# Solar_Points.net
KiCad netlist of a schematic drawn in EAGLE
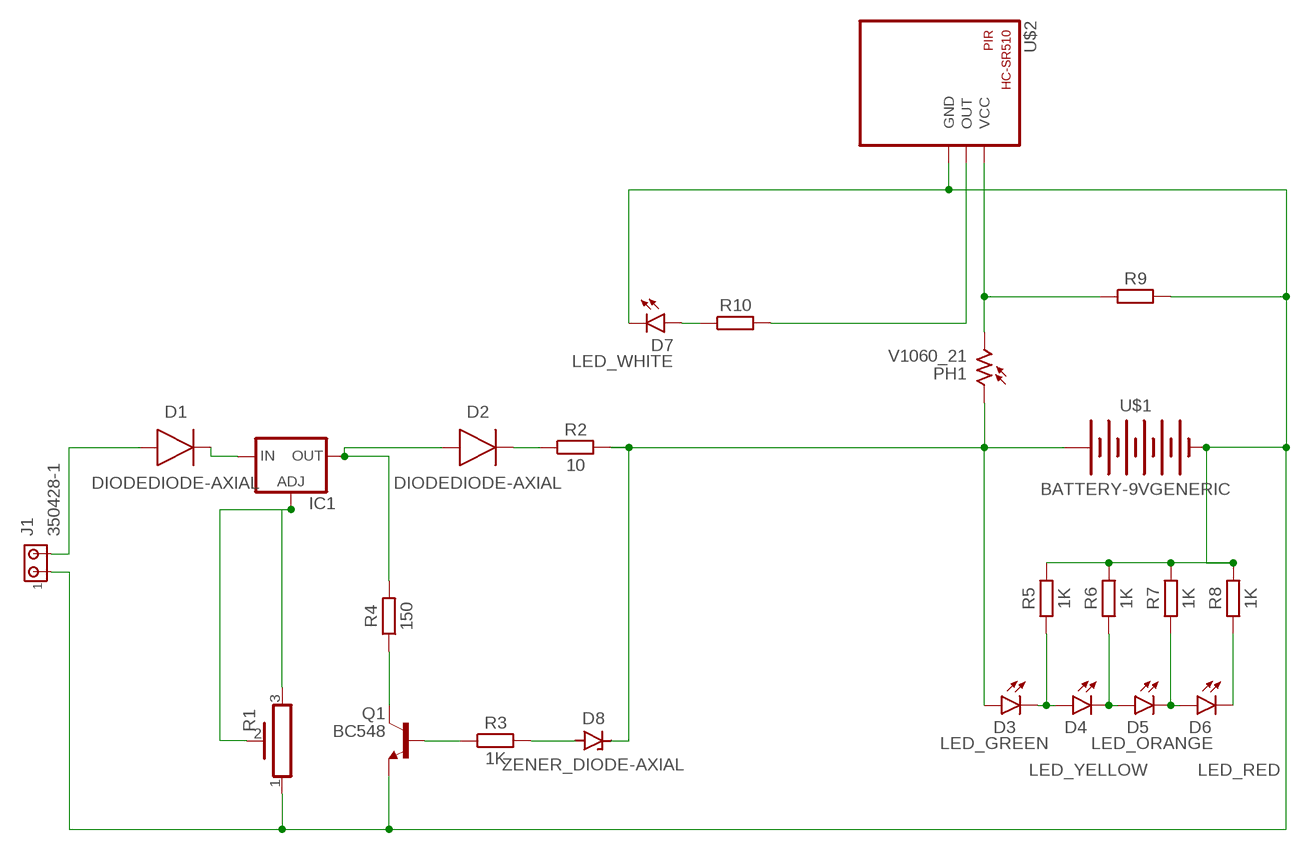
[diagram p0: schematic, sheet 1]

(export (version "E")
  (design (tool "Eeschema 10.0.6"))
  (components
    (comp (ref "D1")
      (value "DIODEDIODE-AXIAL")
      (footprint "eagle-import:DIODE-AXIAL")
      (libsource (lib "eagle-import") (part "DIODEDIODE-AXIAL"))
    )
    (comp (ref "D2")
      (value "DIODEDIODE-AXIAL")
      (footprint "eagle-import:DIODE-AXIAL")
      (libsource (lib "eagle-import") (part "DIODEDIODE-AXIAL"))
    )
    (comp (ref "D3")
      (value "LED_GREEN")
      (footprint "eagle-import:LEDRD254W60D565H860B_G")
      (libsource (lib "eagle-import") (part "LED_RADIALGREEN_"))
    )
    (comp (ref "D4")
      (value "LED_YELLOW")
      (footprint "eagle-import:LEDRD254W60D565H860B_Y")
      (libsource (lib "eagle-import") (part "LED_RADIALYELLOW_"))
    )
    (comp (ref "D5")
      (value "LED_ORANGE")
      (footprint "eagle-import:LEDRD254W60D565H860B_O")
      (libsource (lib "eagle-import") (part "LED_RADIALORANGE_"))
    )
    (comp (ref "D6")
      (value "LED_RED")
      (footprint "eagle-import:LEDRD254W60D565H860B")
      (libsource (lib "eagle-import") (part "LED_RADIALRED_"))
    )
    (comp (ref "D7")
      (value "LED_WHITE")
      (footprint "eagle-import:LEDRD254W60D565H860B_W")
      (libsource (lib "eagle-import") (part "LED_RADIALWHITE_"))
    )
    (comp (ref "D8")
      (value "ZENER_DIODE-AXIAL")
      (footprint "eagle-import:DIODE-AXIAL")
      (libsource (lib "eagle-import") (part "ZENER_DIODE-AXIAL"))
    )
    (comp (ref "IC1")
      (value "LM317TL")
      (footprint "eagle-import:317TL")
      (libsource (lib "eagle-import") (part "LM317TL"))
    )
    (comp (ref "J1")
      (value "350428-1")
      (footprint "eagle-import:350428-1")
      (libsource (lib "eagle-import") (part "350428-1"))
    )
    (comp (ref "PH1")
      (value "V1060_21")
      (footprint "eagle-import:TO-5_V10")
      (libsource (lib "eagle-import") (part "?1060V_21"))
    )
    (comp (ref "Q1")
      (value "BC548")
      (footprint "eagle-import:TO92")
      (libsource (lib "eagle-import") (part "NPN_TO92_"))
    )
    (comp (ref "R1")
      (value "POT_PV36Z")
      (footprint "eagle-import:PV36Z")
      (fields (field (name "MANUFACTURER") "BOURNS") (field (name "MPN") "PV36Z"))
      (libsource (lib "eagle-import") (part "POT_PV36Z"))
    )
    (comp (ref "R2")
      (value "10")
      (footprint "eagle-import:RESAD1176W63L850D250B")
      (libsource (lib "eagle-import") (part "RESISTOR_AXIAL-11.7MM-PITCH_"))
    )
    (comp (ref "R3")
      (value "1K")
      (footprint "eagle-import:RESAD1176W63L850D250B")
      (libsource (lib "eagle-import") (part "RESISTOR_AXIAL-11.7MM-PITCH_"))
    )
    (comp (ref "R4")
      (value "150")
      (footprint "eagle-import:RESAD1176W63L850D250B")
      (libsource (lib "eagle-import") (part "RESISTOR_AXIAL-11.7MM-PITCH_"))
    )
    (comp (ref "R5")
      (value "1K")
      (footprint "eagle-import:RESAD1176W63L850D250B")
      (libsource (lib "eagle-import") (part "RESISTOR_AXIAL-11.7MM-PITCH_"))
    )
    (comp (ref "R6")
      (value "1K")
      (footprint "eagle-import:RESAD1176W63L850D250B")
      (libsource (lib "eagle-import") (part "RESISTOR_AXIAL-11.7MM-PITCH_"))
    )
    (comp (ref "R7")
      (value "1K")
      (footprint "eagle-import:RESAD1176W63L850D250B")
      (libsource (lib "eagle-import") (part "RESISTOR_AXIAL-11.7MM-PITCH_"))
    )
    (comp (ref "R8")
      (value "1K")
      (footprint "eagle-import:RESAD1176W63L850D250B")
      (libsource (lib "eagle-import") (part "RESISTOR_AXIAL-11.7MM-PITCH_"))
    )
    (comp (ref "R9")
      (value "RESISTOR__AXIAL-11.7MM-PITCH")
      (footprint "eagle-import:RESAD1176W63L850D250B")
      (libsource (lib "eagle-import") (part "RESISTOR_AXIAL-11.7MM-PITCH_"))
    )
    (comp (ref "R10")
      (value "RESISTOR__AXIAL-11.7MM-PITCH")
      (footprint "eagle-import:RESAD1176W63L850D250B")
      (libsource (lib "eagle-import") (part "RESISTOR_AXIAL-11.7MM-PITCH_"))
    )
    (comp (ref "U$1")
      (value "BATTERY-9VGENERIC")
      (footprint "eagle-import:BATTERY-GENERIC")
      (libsource (lib "eagle-import") (part "BATTERY-9VGENERIC"))
    )
    (comp (ref "U$2")
      (value "HC-SR501")
      (footprint "eagle-import:HC-SR501")
      (libsource (lib "eagle-import") (part "HC-SR501"))
    )
  )
  (nets
    (net (code "1") (name "Net-(D1-A)") (class "Default")
      (node (ref "D1") (pin "1") (pinfunction "A_1") (pintype "passive"))
      (node (ref "J1") (pin "2") (pinfunction "2_2") (pintype "passive"))
    )
    (net (code "2") (name "Net-(D1-C)") (class "Default")
      (node (ref "D1") (pin "2") (pinfunction "C_2") (pintype "passive"))
      (node (ref "IC1") (pin "3") (pinfunction "IN_3") (pintype "input"))
    )
    (net (code "3") (name "Net-(D2-A)") (class "Default")
      (node (ref "D2") (pin "1") (pinfunction "A_1") (pintype "passive"))
      (node (ref "IC1") (pin "2") (pinfunction "OUT_2") (pintype "passive"))
      (node (ref "R4") (pin "2") (pinfunction "2_2") (pintype "passive"))
    )
    (net (code "4") (name "Net-(D2-C)") (class "Default")
      (node (ref "D2") (pin "2") (pinfunction "C_2") (pintype "passive"))
      (node (ref "R2") (pin "1") (pinfunction "1_1") (pintype "passive"))
    )
    (net (code "5") (name "Net-(D3-A)") (class "Default")
      (node (ref "D3") (pin "1") (pinfunction "A_1") (pintype "passive"))
      (node (ref "D8") (pin "2") (pinfunction "C_2") (pintype "passive"))
      (node (ref "PH1") (pin "1") (pinfunction "1_1") (pintype "passive"))
      (node (ref "R2") (pin "2") (pinfunction "2_2") (pintype "passive"))
      (node (ref "U$1") (pin "+") (pinfunction "+_+") (pintype "passive"))
    )
    (net (code "6") (name "Net-(D3-C)") (class "Default")
      (node (ref "D3") (pin "2") (pinfunction "C_2") (pintype "passive"))
      (node (ref "D4") (pin "1") (pinfunction "A_1") (pintype "passive"))
      (node (ref "R5") (pin "1") (pinfunction "1_1") (pintype "passive"))
    )
    (net (code "7") (name "Net-(D4-C)") (class "Default")
      (node (ref "D4") (pin "2") (pinfunction "C_2") (pintype "passive"))
      (node (ref "D5") (pin "1") (pinfunction "A_1") (pintype "passive"))
      (node (ref "R6") (pin "1") (pinfunction "1_1") (pintype "passive"))
    )
    (net (code "8") (name "Net-(D5-C)") (class "Default")
      (node (ref "D5") (pin "2") (pinfunction "C_2") (pintype "passive"))
      (node (ref "D6") (pin "1") (pinfunction "A_1") (pintype "passive"))
      (node (ref "R7") (pin "1") (pinfunction "1_1") (pintype "passive"))
    )
    (net (code "9") (name "Net-(D6-C)") (class "Default")
      (node (ref "D6") (pin "2") (pinfunction "C_2") (pintype "passive"))
      (node (ref "R8") (pin "1") (pinfunction "1_1") (pintype "passive"))
    )
    (net (code "10") (name "Net-(D7-A)") (class "Default")
      (node (ref "D7") (pin "1") (pinfunction "A_1") (pintype "passive"))
      (node (ref "R10") (pin "1") (pinfunction "1_1") (pintype "passive"))
    )
    (net (code "11") (name "Net-(D7-C)") (class "Default")
      (node (ref "D7") (pin "2") (pinfunction "C_2") (pintype "passive"))
      (node (ref "J1") (pin "1") (pinfunction "1_1") (pintype "passive"))
      (node (ref "Q1") (pin "3") (pinfunction "E_3") (pintype "passive"))
      (node (ref "R1") (pin "1") (pinfunction "P$1_1") (pintype "passive"))
      (node (ref "R5") (pin "2") (pinfunction "2_2") (pintype "passive"))
      (node (ref "R6") (pin "2") (pinfunction "2_2") (pintype "passive"))
      (node (ref "R7") (pin "2") (pinfunction "2_2") (pintype "passive"))
      (node (ref "R8") (pin "2") (pinfunction "2_2") (pintype "passive"))
      (node (ref "R9") (pin "2") (pinfunction "2_2") (pintype "passive"))
      (node (ref "U$1") (pin "-") (pinfunction "-_-") (pintype "passive"))
      (node (ref "U$2") (pin "GND") (pinfunction "GND_GND") (pintype "power_in"))
    )
    (net (code "12") (name "Net-(D8-A)") (class "Default")
      (node (ref "D8") (pin "1") (pinfunction "A_1") (pintype "passive"))
      (node (ref "R3") (pin "2") (pinfunction "2_2") (pintype "passive"))
    )
    (net (code "13") (name "Net-(IC1-ADJ)") (class "Default")
      (node (ref "IC1") (pin "1") (pinfunction "ADJ_1") (pintype "input"))
      (node (ref "R1") (pin "2") (pinfunction "P$2_2") (pintype "passive"))
      (node (ref "R1") (pin "3") (pinfunction "P$3_3") (pintype "passive"))
    )
    (net (code "14") (name "Net-(PH1-Pad2)") (class "Default")
      (node (ref "PH1") (pin "2") (pinfunction "2_2") (pintype "passive"))
      (node (ref "R9") (pin "1") (pinfunction "1_1") (pintype "passive"))
      (node (ref "U$2") (pin "VCC") (pinfunction "VCC_VCC") (pintype "power_in"))
    )
    (net (code "15") (name "Net-(Q1-B)") (class "Default")
      (node (ref "Q1") (pin "2") (pinfunction "B_2") (pintype "passive"))
      (node (ref "R3") (pin "1") (pinfunction "1_1") (pintype "passive"))
    )
    (net (code "16") (name "Net-(Q1-C)") (class "Default")
      (node (ref "Q1") (pin "1") (pinfunction "C_1") (pintype "passive"))
      (node (ref "R4") (pin "1") (pinfunction "1_1") (pintype "passive"))
    )
    (net (code "17") (name "Net-(R10-Pad2)") (class "Default")
      (node (ref "R10") (pin "2") (pinfunction "2_2") (pintype "passive"))
      (node (ref "U$2") (pin "OUT") (pinfunction "OUT_OUT") (pintype "bidirectional"))
    )
  )
)
